# BIT_3.net
KiCad netlist of a schematic drawn in EasyEDA
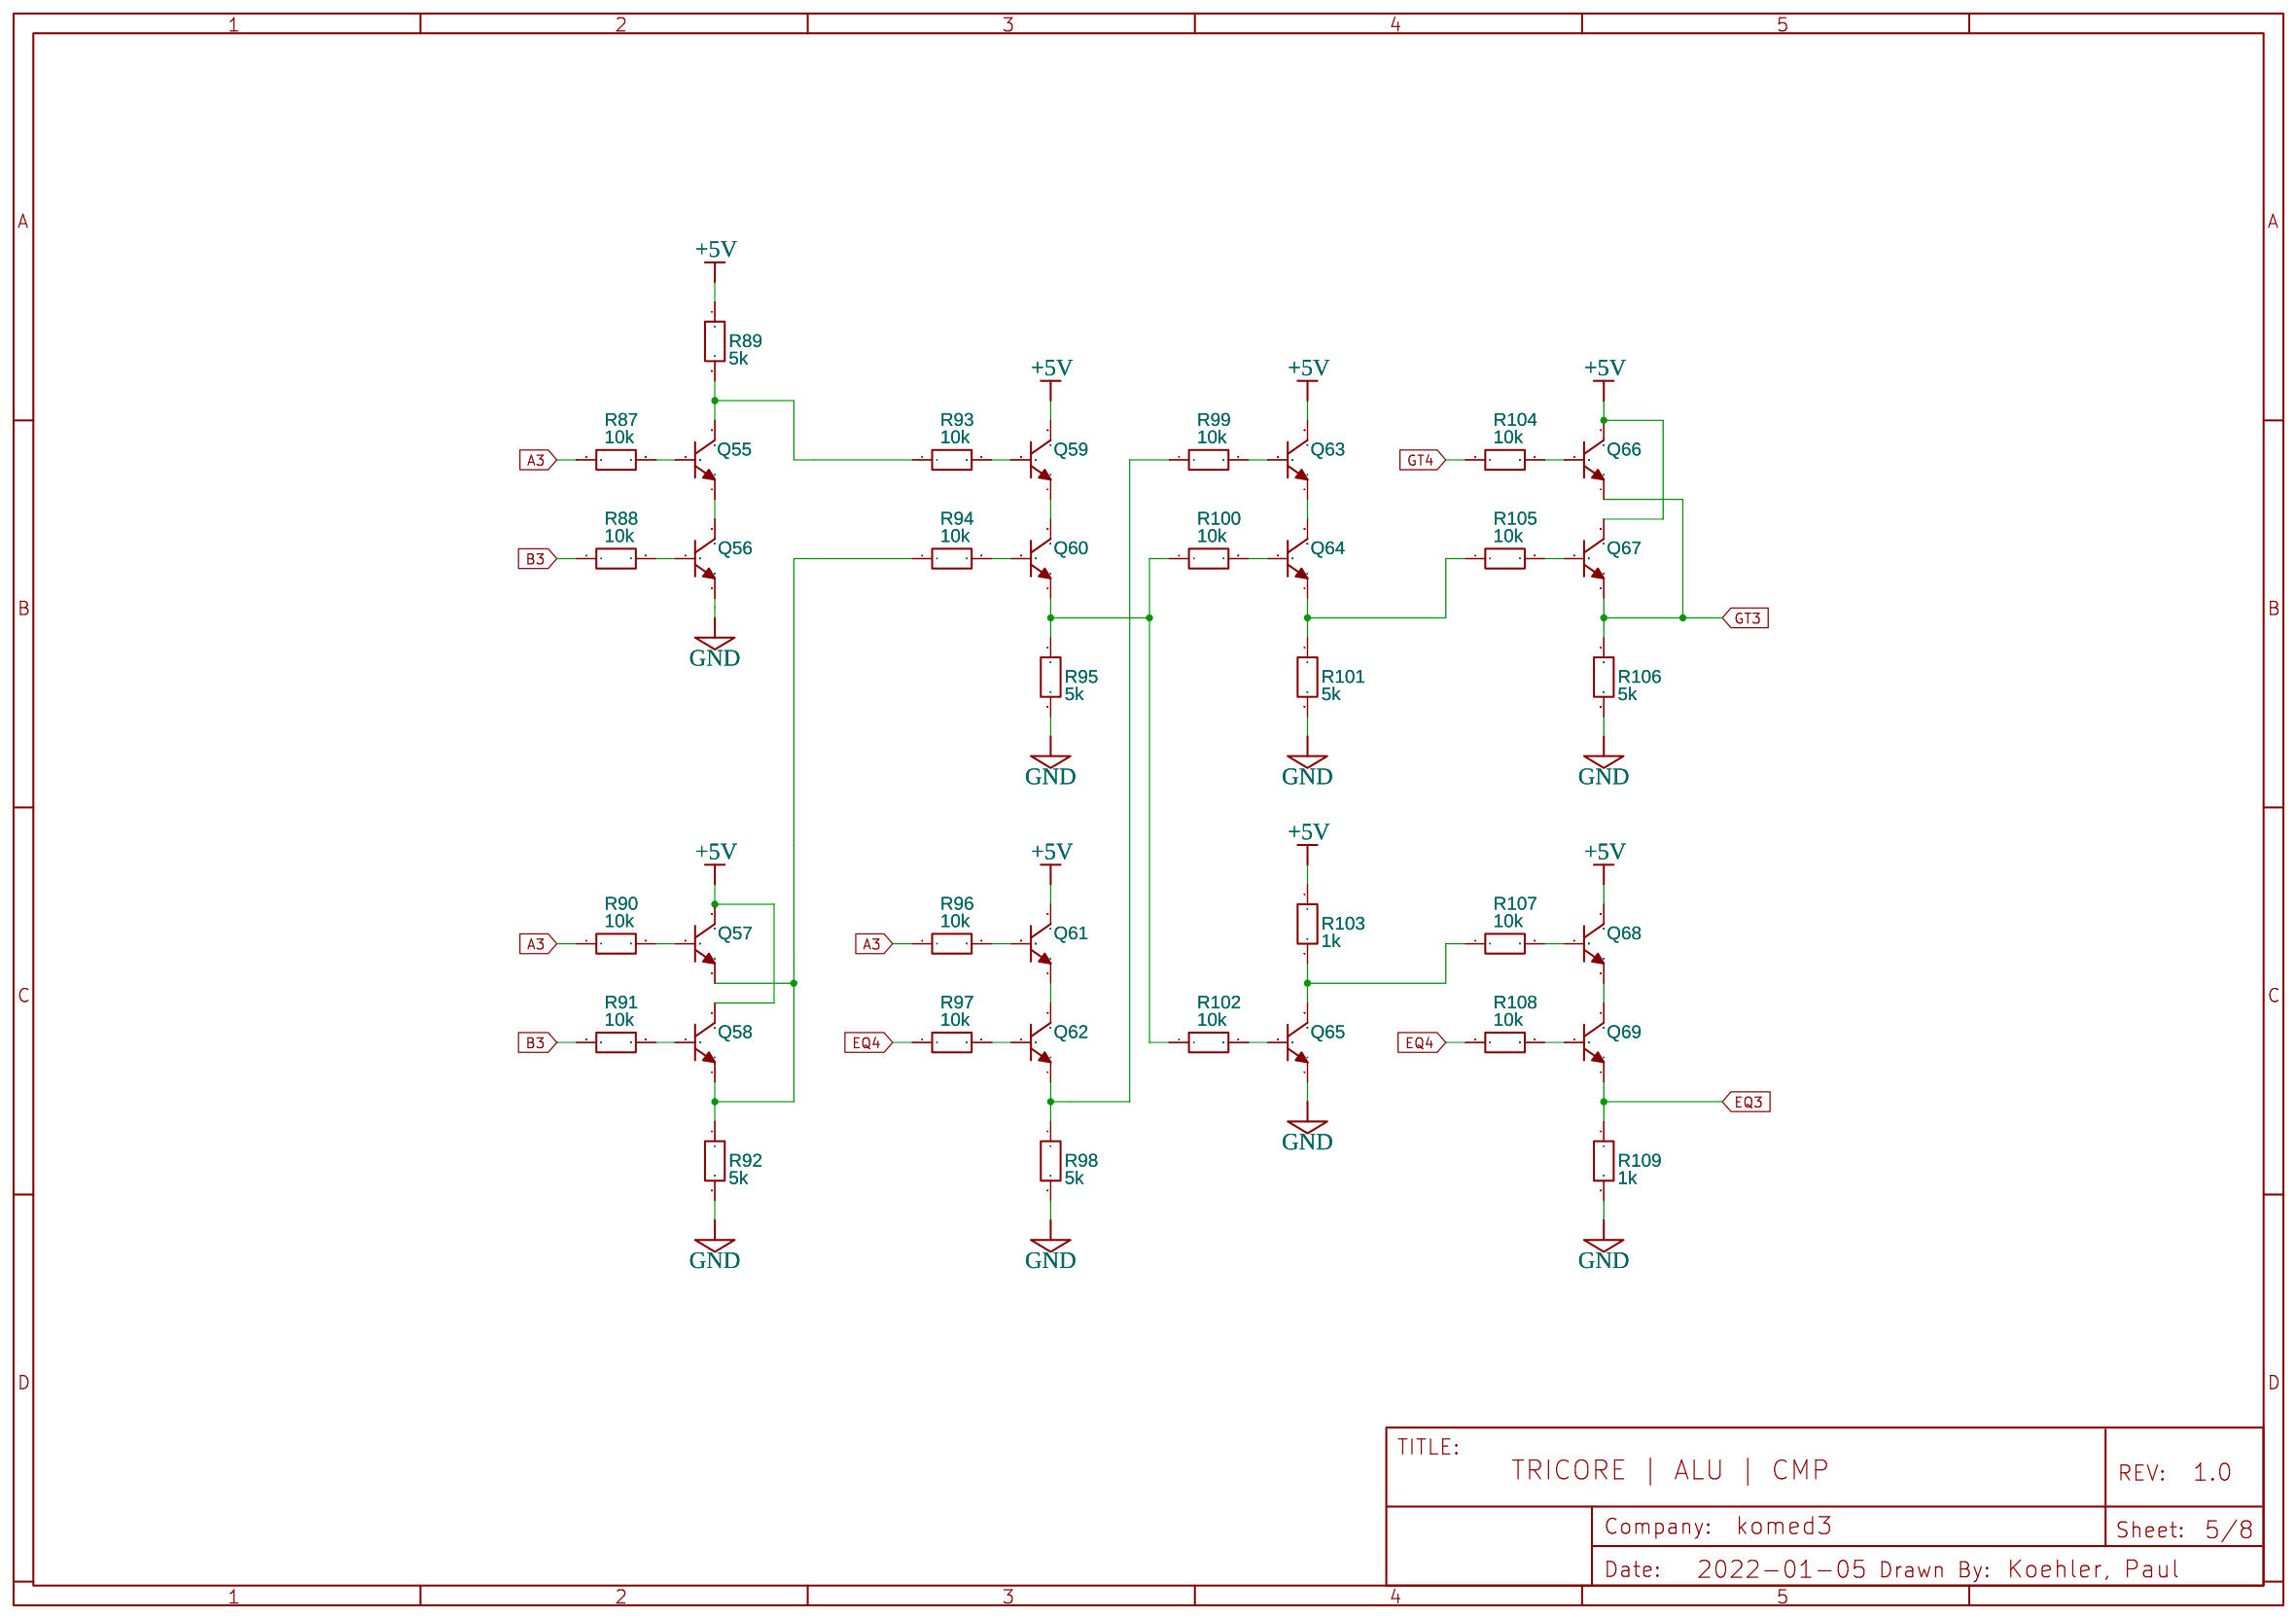
[diagram p0: schematic sheet]

(export (version "E")
  (design (tool "Eeschema 10.0.6"))
  (components
    (comp (ref "Q55")
      (value "2N3904(TO-92)")
      (fields (field (name "BOM_Manufacturer Part") "2N3904") (field (name "BOM_Supplier Part") "C118538"))
      (libsource (lib "") (part "2N3904(TO-92)"))
    )
    (comp (ref "Q56")
      (value "2N3904(TO-92)")
      (fields (field (name "BOM_Manufacturer Part") "2N3904") (field (name "BOM_Supplier Part") "C118538"))
      (libsource (lib "") (part "2N3904(TO-92)"))
    )
    (comp (ref "Q57")
      (value "2N3904(TO-92)")
      (fields (field (name "BOM_Manufacturer Part") "2N3904") (field (name "BOM_Supplier Part") "C118538"))
      (libsource (lib "") (part "2N3904(TO-92)"))
    )
    (comp (ref "Q58")
      (value "2N3904(TO-92)")
      (fields (field (name "BOM_Manufacturer Part") "2N3904") (field (name "BOM_Supplier Part") "C118538"))
      (libsource (lib "") (part "2N3904(TO-92)"))
    )
    (comp (ref "Q59")
      (value "2N3904(TO-92)")
      (fields (field (name "BOM_Manufacturer Part") "2N3904") (field (name "BOM_Supplier Part") "C118538"))
      (libsource (lib "") (part "2N3904(TO-92)"))
    )
    (comp (ref "Q60")
      (value "2N3904(TO-92)")
      (fields (field (name "BOM_Manufacturer Part") "2N3904") (field (name "BOM_Supplier Part") "C118538"))
      (libsource (lib "") (part "2N3904(TO-92)"))
    )
    (comp (ref "Q61")
      (value "2N3904(TO-92)")
      (fields (field (name "BOM_Manufacturer Part") "2N3904") (field (name "BOM_Supplier Part") "C118538"))
      (libsource (lib "") (part "2N3904(TO-92)"))
    )
    (comp (ref "Q62")
      (value "2N3904(TO-92)")
      (fields (field (name "BOM_Manufacturer Part") "2N3904") (field (name "BOM_Supplier Part") "C118538"))
      (libsource (lib "") (part "2N3904(TO-92)"))
    )
    (comp (ref "Q63")
      (value "2N3904(TO-92)")
      (fields (field (name "BOM_Manufacturer Part") "2N3904") (field (name "BOM_Supplier Part") "C118538"))
      (libsource (lib "") (part "2N3904(TO-92)"))
    )
    (comp (ref "Q64")
      (value "2N3904(TO-92)")
      (fields (field (name "BOM_Manufacturer Part") "2N3904") (field (name "BOM_Supplier Part") "C118538"))
      (libsource (lib "") (part "2N3904(TO-92)"))
    )
    (comp (ref "Q65")
      (value "2N3904(TO-92)")
      (fields (field (name "BOM_Manufacturer Part") "2N3904") (field (name "BOM_Supplier Part") "C118538"))
      (libsource (lib "") (part "2N3904(TO-92)"))
    )
    (comp (ref "Q66")
      (value "2N3904(TO-92)")
      (fields (field (name "BOM_Manufacturer Part") "2N3904") (field (name "BOM_Supplier Part") "C118538"))
      (libsource (lib "") (part "2N3904(TO-92)"))
    )
    (comp (ref "Q67")
      (value "2N3904(TO-92)")
      (fields (field (name "BOM_Manufacturer Part") "2N3904") (field (name "BOM_Supplier Part") "C118538"))
      (libsource (lib "") (part "2N3904(TO-92)"))
    )
    (comp (ref "Q68")
      (value "2N3904(TO-92)")
      (fields (field (name "BOM_Manufacturer Part") "2N3904") (field (name "BOM_Supplier Part") "C118538"))
      (libsource (lib "") (part "2N3904(TO-92)"))
    )
    (comp (ref "Q69")
      (value "2N3904(TO-92)")
      (fields (field (name "BOM_Manufacturer Part") "2N3904") (field (name "BOM_Supplier Part") "C118538"))
      (libsource (lib "") (part "2N3904(TO-92)"))
    )
    (comp (ref "R87") (value "10k") (libsource (lib "") (part "R_AXIAL-0.3_EU")))
    (comp (ref "R88") (value "10k") (libsource (lib "") (part "R_AXIAL-0.3_EU")))
    (comp (ref "R89") (value "5k") (libsource (lib "") (part "R_AXIAL-0.3_EU_1")))
    (comp (ref "R90") (value "10k") (libsource (lib "") (part "R_AXIAL-0.3_EU")))
    (comp (ref "R91") (value "10k") (libsource (lib "") (part "R_AXIAL-0.3_EU")))
    (comp (ref "R92") (value "5k") (libsource (lib "") (part "R_AXIAL-0.3_EU_1")))
    (comp (ref "R93") (value "10k") (libsource (lib "") (part "R_AXIAL-0.3_EU")))
    (comp (ref "R94") (value "10k") (libsource (lib "") (part "R_AXIAL-0.3_EU")))
    (comp (ref "R95") (value "5k") (libsource (lib "") (part "R_AXIAL-0.3_EU_1")))
    (comp (ref "R96") (value "10k") (libsource (lib "") (part "R_AXIAL-0.3_EU")))
    (comp (ref "R97") (value "10k") (libsource (lib "") (part "R_AXIAL-0.3_EU")))
    (comp (ref "R98") (value "5k") (libsource (lib "") (part "R_AXIAL-0.3_EU_1")))
    (comp (ref "R99") (value "10k") (libsource (lib "") (part "R_AXIAL-0.3_EU")))
    (comp (ref "R100") (value "10k") (libsource (lib "") (part "R_AXIAL-0.3_EU")))
    (comp (ref "R101") (value "5k") (libsource (lib "") (part "R_AXIAL-0.3_EU_1")))
    (comp (ref "R102") (value "10k") (libsource (lib "") (part "R_AXIAL-0.3_EU")))
    (comp (ref "R103") (value "1k") (libsource (lib "") (part "R_AXIAL-0.3_EU_1")))
    (comp (ref "R104") (value "10k") (libsource (lib "") (part "R_AXIAL-0.3_EU")))
    (comp (ref "R105") (value "10k") (libsource (lib "") (part "R_AXIAL-0.3_EU")))
    (comp (ref "R106") (value "5k") (libsource (lib "") (part "R_AXIAL-0.3_EU_1")))
    (comp (ref "R107") (value "10k") (libsource (lib "") (part "R_AXIAL-0.3_EU")))
    (comp (ref "R108") (value "10k") (libsource (lib "") (part "R_AXIAL-0.3_EU")))
    (comp (ref "R109") (value "1k") (libsource (lib "") (part "R_AXIAL-0.3_EU_1")))
  )
  (nets
    (net (code "1") (name "+5V") (class "Default")
      (node (ref "Q57") (pin "3") (pinfunction "C_3") (pintype "unspecified"))
      (node (ref "Q58") (pin "3") (pinfunction "C_3") (pintype "unspecified"))
      (node (ref "Q59") (pin "3") (pinfunction "C_3") (pintype "unspecified"))
      (node (ref "Q61") (pin "3") (pinfunction "C_3") (pintype "unspecified"))
      (node (ref "Q63") (pin "3") (pinfunction "C_3") (pintype "unspecified"))
      (node (ref "Q66") (pin "3") (pinfunction "C_3") (pintype "unspecified"))
      (node (ref "Q67") (pin "3") (pinfunction "C_3") (pintype "unspecified"))
      (node (ref "Q68") (pin "3") (pinfunction "C_3") (pintype "unspecified"))
      (node (ref "R103") (pin "1") (pinfunction "1_1") (pintype "unspecified"))
      (node (ref "R89") (pin "1") (pinfunction "1_1") (pintype "unspecified"))
    )
    (net (code "2") (name "A3") (class "Default")
      (node (ref "R87") (pin "1") (pinfunction "1_1") (pintype "unspecified"))
      (node (ref "R90") (pin "1") (pinfunction "1_1") (pintype "unspecified"))
      (node (ref "R96") (pin "1") (pinfunction "1_1") (pintype "unspecified"))
    )
    (net (code "3") (name "B3") (class "Default")
      (node (ref "R88") (pin "1") (pinfunction "1_1") (pintype "unspecified"))
      (node (ref "R91") (pin "1") (pinfunction "1_1") (pintype "unspecified"))
    )
    (net (code "4") (name "EQ3") (class "Default")
      (node (ref "Q69") (pin "1") (pinfunction "E_1") (pintype "unspecified"))
      (node (ref "R109") (pin "1") (pinfunction "1_1") (pintype "unspecified"))
    )
    (net (code "5") (name "EQ4") (class "Default")
      (node (ref "R108") (pin "1") (pinfunction "1_1") (pintype "unspecified"))
      (node (ref "R97") (pin "1") (pinfunction "1_1") (pintype "unspecified"))
    )
    (net (code "6") (name "GND") (class "Default")
      (node (ref "Q56") (pin "1") (pinfunction "E_1") (pintype "unspecified"))
      (node (ref "Q65") (pin "1") (pinfunction "E_1") (pintype "unspecified"))
      (node (ref "R101") (pin "2") (pinfunction "2_2") (pintype "unspecified"))
      (node (ref "R106") (pin "2") (pinfunction "2_2") (pintype "unspecified"))
      (node (ref "R109") (pin "2") (pinfunction "2_2") (pintype "unspecified"))
      (node (ref "R92") (pin "2") (pinfunction "2_2") (pintype "unspecified"))
      (node (ref "R95") (pin "2") (pinfunction "2_2") (pintype "unspecified"))
      (node (ref "R98") (pin "2") (pinfunction "2_2") (pintype "unspecified"))
    )
    (net (code "7") (name "GT3") (class "Default")
      (node (ref "Q66") (pin "1") (pinfunction "E_1") (pintype "unspecified"))
      (node (ref "Q67") (pin "1") (pinfunction "E_1") (pintype "unspecified"))
      (node (ref "R106") (pin "1") (pinfunction "1_1") (pintype "unspecified"))
    )
    (net (code "8") (name "GT4") (class "Default")
      (node (ref "R104") (pin "1") (pinfunction "1_1") (pintype "unspecified"))
    )
    (net (code "9") (name "Net-(Q55-B)") (class "Default")
      (node (ref "Q55") (pin "2") (pinfunction "B_2") (pintype "unspecified"))
      (node (ref "R87") (pin "2") (pinfunction "2_2") (pintype "unspecified"))
    )
    (net (code "10") (name "Net-(Q55-C)") (class "Default")
      (node (ref "Q55") (pin "3") (pinfunction "C_3") (pintype "unspecified"))
      (node (ref "R89") (pin "2") (pinfunction "2_2") (pintype "unspecified"))
      (node (ref "R93") (pin "1") (pinfunction "1_1") (pintype "unspecified"))
    )
    (net (code "11") (name "Net-(Q55-E)") (class "Default")
      (node (ref "Q55") (pin "1") (pinfunction "E_1") (pintype "unspecified"))
      (node (ref "Q56") (pin "3") (pinfunction "C_3") (pintype "unspecified"))
    )
    (net (code "12") (name "Net-(Q56-B)") (class "Default")
      (node (ref "Q56") (pin "2") (pinfunction "B_2") (pintype "unspecified"))
      (node (ref "R88") (pin "2") (pinfunction "2_2") (pintype "unspecified"))
    )
    (net (code "13") (name "Net-(Q57-B)") (class "Default")
      (node (ref "Q57") (pin "2") (pinfunction "B_2") (pintype "unspecified"))
      (node (ref "R90") (pin "2") (pinfunction "2_2") (pintype "unspecified"))
    )
    (net (code "14") (name "Net-(Q57-E)") (class "Default")
      (node (ref "Q57") (pin "1") (pinfunction "E_1") (pintype "unspecified"))
      (node (ref "Q58") (pin "1") (pinfunction "E_1") (pintype "unspecified"))
      (node (ref "R92") (pin "1") (pinfunction "1_1") (pintype "unspecified"))
      (node (ref "R94") (pin "1") (pinfunction "1_1") (pintype "unspecified"))
    )
    (net (code "15") (name "Net-(Q58-B)") (class "Default")
      (node (ref "Q58") (pin "2") (pinfunction "B_2") (pintype "unspecified"))
      (node (ref "R91") (pin "2") (pinfunction "2_2") (pintype "unspecified"))
    )
    (net (code "16") (name "Net-(Q59-B)") (class "Default")
      (node (ref "Q59") (pin "2") (pinfunction "B_2") (pintype "unspecified"))
      (node (ref "R93") (pin "2") (pinfunction "2_2") (pintype "unspecified"))
    )
    (net (code "17") (name "Net-(Q59-E)") (class "Default")
      (node (ref "Q59") (pin "1") (pinfunction "E_1") (pintype "unspecified"))
      (node (ref "Q60") (pin "3") (pinfunction "C_3") (pintype "unspecified"))
    )
    (net (code "18") (name "Net-(Q60-B)") (class "Default")
      (node (ref "Q60") (pin "2") (pinfunction "B_2") (pintype "unspecified"))
      (node (ref "R94") (pin "2") (pinfunction "2_2") (pintype "unspecified"))
    )
    (net (code "19") (name "Net-(Q60-E)") (class "Default")
      (node (ref "Q60") (pin "1") (pinfunction "E_1") (pintype "unspecified"))
      (node (ref "R100") (pin "1") (pinfunction "1_1") (pintype "unspecified"))
      (node (ref "R102") (pin "1") (pinfunction "1_1") (pintype "unspecified"))
      (node (ref "R95") (pin "1") (pinfunction "1_1") (pintype "unspecified"))
    )
    (net (code "20") (name "Net-(Q61-B)") (class "Default")
      (node (ref "Q61") (pin "2") (pinfunction "B_2") (pintype "unspecified"))
      (node (ref "R96") (pin "2") (pinfunction "2_2") (pintype "unspecified"))
    )
    (net (code "21") (name "Net-(Q61-E)") (class "Default")
      (node (ref "Q61") (pin "1") (pinfunction "E_1") (pintype "unspecified"))
      (node (ref "Q62") (pin "3") (pinfunction "C_3") (pintype "unspecified"))
    )
    (net (code "22") (name "Net-(Q62-B)") (class "Default")
      (node (ref "Q62") (pin "2") (pinfunction "B_2") (pintype "unspecified"))
      (node (ref "R97") (pin "2") (pinfunction "2_2") (pintype "unspecified"))
    )
    (net (code "23") (name "Net-(Q62-E)") (class "Default")
      (node (ref "Q62") (pin "1") (pinfunction "E_1") (pintype "unspecified"))
      (node (ref "R98") (pin "1") (pinfunction "1_1") (pintype "unspecified"))
      (node (ref "R99") (pin "1") (pinfunction "1_1") (pintype "unspecified"))
    )
    (net (code "24") (name "Net-(Q63-B)") (class "Default")
      (node (ref "Q63") (pin "2") (pinfunction "B_2") (pintype "unspecified"))
      (node (ref "R99") (pin "2") (pinfunction "2_2") (pintype "unspecified"))
    )
    (net (code "25") (name "Net-(Q63-E)") (class "Default")
      (node (ref "Q63") (pin "1") (pinfunction "E_1") (pintype "unspecified"))
      (node (ref "Q64") (pin "3") (pinfunction "C_3") (pintype "unspecified"))
    )
    (net (code "26") (name "Net-(Q64-B)") (class "Default")
      (node (ref "Q64") (pin "2") (pinfunction "B_2") (pintype "unspecified"))
      (node (ref "R100") (pin "2") (pinfunction "2_2") (pintype "unspecified"))
    )
    (net (code "27") (name "Net-(Q64-E)") (class "Default")
      (node (ref "Q64") (pin "1") (pinfunction "E_1") (pintype "unspecified"))
      (node (ref "R101") (pin "1") (pinfunction "1_1") (pintype "unspecified"))
      (node (ref "R105") (pin "1") (pinfunction "1_1") (pintype "unspecified"))
    )
    (net (code "28") (name "Net-(Q65-B)") (class "Default")
      (node (ref "Q65") (pin "2") (pinfunction "B_2") (pintype "unspecified"))
      (node (ref "R102") (pin "2") (pinfunction "2_2") (pintype "unspecified"))
    )
    (net (code "29") (name "Net-(Q65-C)") (class "Default")
      (node (ref "Q65") (pin "3") (pinfunction "C_3") (pintype "unspecified"))
      (node (ref "R103") (pin "2") (pinfunction "2_2") (pintype "unspecified"))
      (node (ref "R107") (pin "1") (pinfunction "1_1") (pintype "unspecified"))
    )
    (net (code "30") (name "Net-(Q66-B)") (class "Default")
      (node (ref "Q66") (pin "2") (pinfunction "B_2") (pintype "unspecified"))
      (node (ref "R104") (pin "2") (pinfunction "2_2") (pintype "unspecified"))
    )
    (net (code "31") (name "Net-(Q67-B)") (class "Default")
      (node (ref "Q67") (pin "2") (pinfunction "B_2") (pintype "unspecified"))
      (node (ref "R105") (pin "2") (pinfunction "2_2") (pintype "unspecified"))
    )
    (net (code "32") (name "Net-(Q68-B)") (class "Default")
      (node (ref "Q68") (pin "2") (pinfunction "B_2") (pintype "unspecified"))
      (node (ref "R107") (pin "2") (pinfunction "2_2") (pintype "unspecified"))
    )
    (net (code "33") (name "Net-(Q68-E)") (class "Default")
      (node (ref "Q68") (pin "1") (pinfunction "E_1") (pintype "unspecified"))
      (node (ref "Q69") (pin "3") (pinfunction "C_3") (pintype "unspecified"))
    )
    (net (code "34") (name "Net-(Q69-B)") (class "Default")
      (node (ref "Q69") (pin "2") (pinfunction "B_2") (pintype "unspecified"))
      (node (ref "R108") (pin "2") (pinfunction "2_2") (pintype "unspecified"))
    )
  )
)
